# pci-con.net
KiCad netlist of a schematic drawn in EAGLE
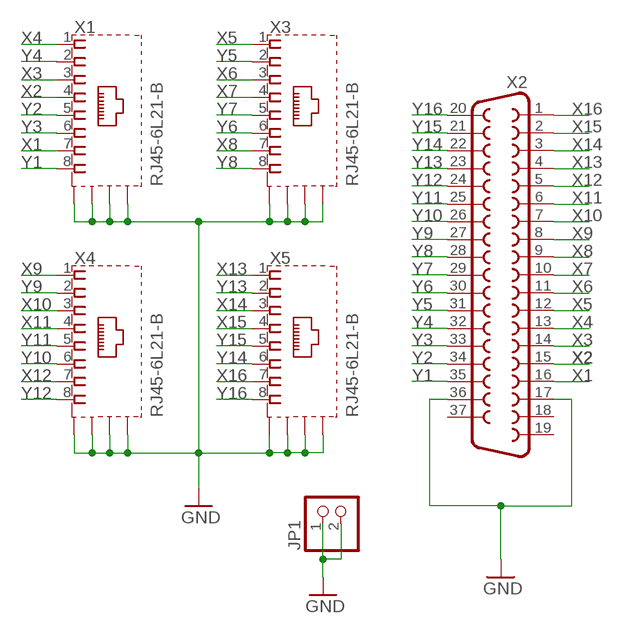
[diagram p0: schematic, sheet 1]

(export (version "E")
  (design (tool "Eeschema 10.0.6"))
  (components
    (comp (ref "JP1")
      (value "PINHD-1X2")
      (footprint "eagle-import:1X02")
      (libsource (lib "eagle-import") (part "PINHD-1X2"))
    )
    (comp (ref "X1")
      (value "RJ45-6L21-B")
      (footprint "eagle-import:RJ45-SHIELD1")
      (libsource (lib "eagle-import") (part "RJ4521-B-6L"))
    )
    (comp (ref "X2")
      (value "F37HP")
      (footprint "eagle-import:F37HP")
      (libsource (lib "eagle-import") (part "F37HP"))
    )
    (comp (ref "X3")
      (value "RJ45-6L21-B")
      (footprint "eagle-import:RJ45-SHIELD1")
      (libsource (lib "eagle-import") (part "RJ4521-B-6L"))
    )
    (comp (ref "X4")
      (value "RJ45-6L21-B")
      (footprint "eagle-import:RJ45-SHIELD1")
      (libsource (lib "eagle-import") (part "RJ4521-B-6L"))
    )
    (comp (ref "X5")
      (value "RJ45-6L21-B")
      (footprint "eagle-import:RJ45-SHIELD1")
      (libsource (lib "eagle-import") (part "RJ4521-B-6L"))
    )
  )
  (nets
    (net (code "1") (name "/X1") (class "Default")
      (node (ref "X1") (pin "7") (pinfunction "7_7") (pintype "passive"))
      (node (ref "X2") (pin "16") (pinfunction "16_16") (pintype "passive"))
    )
    (net (code "2") (name "/X2") (class "Default")
      (node (ref "X1") (pin "4") (pinfunction "4_4") (pintype "passive"))
      (node (ref "X2") (pin "15") (pinfunction "15_15") (pintype "passive"))
    )
    (net (code "3") (name "/X3") (class "Default")
      (node (ref "X1") (pin "3") (pinfunction "3_3") (pintype "passive"))
      (node (ref "X2") (pin "14") (pinfunction "14_14") (pintype "passive"))
    )
    (net (code "4") (name "/X4") (class "Default")
      (node (ref "X1") (pin "1") (pinfunction "1_1") (pintype "passive"))
      (node (ref "X2") (pin "13") (pinfunction "13_13") (pintype "passive"))
    )
    (net (code "5") (name "/X5") (class "Default")
      (node (ref "X2") (pin "12") (pinfunction "12_12") (pintype "passive"))
      (node (ref "X3") (pin "1") (pinfunction "1_1") (pintype "passive"))
    )
    (net (code "6") (name "/X6") (class "Default")
      (node (ref "X2") (pin "11") (pinfunction "11_11") (pintype "passive"))
      (node (ref "X3") (pin "3") (pinfunction "3_3") (pintype "passive"))
    )
    (net (code "7") (name "/X7") (class "Default")
      (node (ref "X2") (pin "10") (pinfunction "10_10") (pintype "passive"))
      (node (ref "X3") (pin "4") (pinfunction "4_4") (pintype "passive"))
    )
    (net (code "8") (name "/X8") (class "Default")
      (node (ref "X2") (pin "9") (pinfunction "9_9") (pintype "passive"))
      (node (ref "X3") (pin "7") (pinfunction "7_7") (pintype "passive"))
    )
    (net (code "9") (name "/X9") (class "Default")
      (node (ref "X2") (pin "8") (pinfunction "8_8") (pintype "passive"))
      (node (ref "X4") (pin "1") (pinfunction "1_1") (pintype "passive"))
    )
    (net (code "10") (name "/X10") (class "Default")
      (node (ref "X2") (pin "7") (pinfunction "7_7") (pintype "passive"))
      (node (ref "X4") (pin "3") (pinfunction "3_3") (pintype "passive"))
    )
    (net (code "11") (name "/X11") (class "Default")
      (node (ref "X2") (pin "6") (pinfunction "6_6") (pintype "passive"))
      (node (ref "X4") (pin "4") (pinfunction "4_4") (pintype "passive"))
    )
    (net (code "12") (name "/X12") (class "Default")
      (node (ref "X2") (pin "5") (pinfunction "5_5") (pintype "passive"))
      (node (ref "X4") (pin "7") (pinfunction "7_7") (pintype "passive"))
    )
    (net (code "13") (name "/X13") (class "Default")
      (node (ref "X2") (pin "4") (pinfunction "4_4") (pintype "passive"))
      (node (ref "X5") (pin "1") (pinfunction "1_1") (pintype "passive"))
    )
    (net (code "14") (name "/X14") (class "Default")
      (node (ref "X2") (pin "3") (pinfunction "3_3") (pintype "passive"))
      (node (ref "X5") (pin "3") (pinfunction "3_3") (pintype "passive"))
    )
    (net (code "15") (name "/X15") (class "Default")
      (node (ref "X2") (pin "2") (pinfunction "2_2") (pintype "passive"))
      (node (ref "X5") (pin "4") (pinfunction "4_4") (pintype "passive"))
    )
    (net (code "16") (name "/X16") (class "Default")
      (node (ref "X2") (pin "1") (pinfunction "1_1") (pintype "passive"))
      (node (ref "X5") (pin "7") (pinfunction "7_7") (pintype "passive"))
    )
    (net (code "17") (name "/Y1") (class "Default")
      (node (ref "X1") (pin "8") (pinfunction "8_8") (pintype "passive"))
      (node (ref "X2") (pin "35") (pinfunction "35_35") (pintype "passive"))
    )
    (net (code "18") (name "/Y2") (class "Default")
      (node (ref "X1") (pin "5") (pinfunction "5_5") (pintype "passive"))
      (node (ref "X2") (pin "34") (pinfunction "34_34") (pintype "passive"))
    )
    (net (code "19") (name "/Y3") (class "Default")
      (node (ref "X1") (pin "6") (pinfunction "6_6") (pintype "passive"))
      (node (ref "X2") (pin "33") (pinfunction "33_33") (pintype "passive"))
    )
    (net (code "20") (name "/Y4") (class "Default")
      (node (ref "X1") (pin "2") (pinfunction "2_2") (pintype "passive"))
      (node (ref "X2") (pin "32") (pinfunction "32_32") (pintype "passive"))
    )
    (net (code "21") (name "/Y5") (class "Default")
      (node (ref "X2") (pin "31") (pinfunction "31_31") (pintype "passive"))
      (node (ref "X3") (pin "2") (pinfunction "2_2") (pintype "passive"))
    )
    (net (code "22") (name "/Y6") (class "Default")
      (node (ref "X2") (pin "30") (pinfunction "30_30") (pintype "passive"))
      (node (ref "X3") (pin "6") (pinfunction "6_6") (pintype "passive"))
    )
    (net (code "23") (name "/Y7") (class "Default")
      (node (ref "X2") (pin "29") (pinfunction "29_29") (pintype "passive"))
      (node (ref "X3") (pin "5") (pinfunction "5_5") (pintype "passive"))
    )
    (net (code "24") (name "/Y8") (class "Default")
      (node (ref "X2") (pin "28") (pinfunction "28_28") (pintype "passive"))
      (node (ref "X3") (pin "8") (pinfunction "8_8") (pintype "passive"))
    )
    (net (code "25") (name "/Y9") (class "Default")
      (node (ref "X2") (pin "27") (pinfunction "27_27") (pintype "passive"))
      (node (ref "X4") (pin "2") (pinfunction "2_2") (pintype "passive"))
    )
    (net (code "26") (name "/Y10") (class "Default")
      (node (ref "X2") (pin "26") (pinfunction "26_26") (pintype "passive"))
      (node (ref "X4") (pin "6") (pinfunction "6_6") (pintype "passive"))
    )
    (net (code "27") (name "/Y11") (class "Default")
      (node (ref "X2") (pin "25") (pinfunction "25_25") (pintype "passive"))
      (node (ref "X4") (pin "5") (pinfunction "5_5") (pintype "passive"))
    )
    (net (code "28") (name "/Y12") (class "Default")
      (node (ref "X2") (pin "24") (pinfunction "24_24") (pintype "passive"))
      (node (ref "X4") (pin "8") (pinfunction "8_8") (pintype "passive"))
    )
    (net (code "29") (name "/Y13") (class "Default")
      (node (ref "X2") (pin "23") (pinfunction "23_23") (pintype "passive"))
      (node (ref "X5") (pin "2") (pinfunction "2_2") (pintype "passive"))
    )
    (net (code "30") (name "/Y14") (class "Default")
      (node (ref "X2") (pin "22") (pinfunction "22_22") (pintype "passive"))
      (node (ref "X5") (pin "6") (pinfunction "6_6") (pintype "passive"))
    )
    (net (code "31") (name "/Y15") (class "Default")
      (node (ref "X2") (pin "21") (pinfunction "21_21") (pintype "passive"))
      (node (ref "X5") (pin "5") (pinfunction "5_5") (pintype "passive"))
    )
    (net (code "32") (name "/Y16") (class "Default")
      (node (ref "X2") (pin "20") (pinfunction "20_20") (pintype "passive"))
      (node (ref "X5") (pin "8") (pinfunction "8_8") (pintype "passive"))
    )
    (net (code "33") (name "GND") (class "Default")
      (node (ref "JP1") (pin "1") (pinfunction "1_1") (pintype "passive"))
      (node (ref "JP1") (pin "2") (pinfunction "2_2") (pintype "passive"))
      (node (ref "X1") (pin "S1") (pinfunction "S_S1") (pintype "passive"))
      (node (ref "X1") (pin "S2") (pinfunction "S_S2") (pintype "passive"))
      (node (ref "X1") (pin "S3") (pinfunction "S_S3") (pintype "passive"))
      (node (ref "X1") (pin "S4") (pinfunction "S_S4") (pintype "passive"))
      (node (ref "X2") (pin "17") (pinfunction "17_17") (pintype "passive"))
      (node (ref "X2") (pin "36") (pinfunction "36_36") (pintype "passive"))
      (node (ref "X3") (pin "S1") (pinfunction "S_S1") (pintype "passive"))
      (node (ref "X3") (pin "S2") (pinfunction "S_S2") (pintype "passive"))
      (node (ref "X3") (pin "S3") (pinfunction "S_S3") (pintype "passive"))
      (node (ref "X3") (pin "S4") (pinfunction "S_S4") (pintype "passive"))
      (node (ref "X4") (pin "S1") (pinfunction "S_S1") (pintype "passive"))
      (node (ref "X4") (pin "S2") (pinfunction "S_S2") (pintype "passive"))
      (node (ref "X4") (pin "S3") (pinfunction "S_S3") (pintype "passive"))
      (node (ref "X4") (pin "S4") (pinfunction "S_S4") (pintype "passive"))
      (node (ref "X5") (pin "S1") (pinfunction "S_S1") (pintype "passive"))
      (node (ref "X5") (pin "S2") (pinfunction "S_S2") (pintype "passive"))
      (node (ref "X5") (pin "S3") (pinfunction "S_S3") (pintype "passive"))
      (node (ref "X5") (pin "S4") (pinfunction "S_S4") (pintype "passive"))
    )
    (net (code "34") (name "unconnected-(X2-Pad18)") (class "Default")
      (node (ref "X2") (pin "18") (pinfunction "18_18") (pintype "passive"))
    )
    (net (code "35") (name "unconnected-(X2-Pad19)") (class "Default")
      (node (ref "X2") (pin "19") (pinfunction "19_19") (pintype "passive"))
    )
    (net (code "36") (name "unconnected-(X2-Pad37)") (class "Default")
      (node (ref "X2") (pin "37") (pinfunction "37_37") (pintype "passive"))
    )
  )
)
